# Radio.net
KiCad netlist of a schematic drawn in Altium Designer
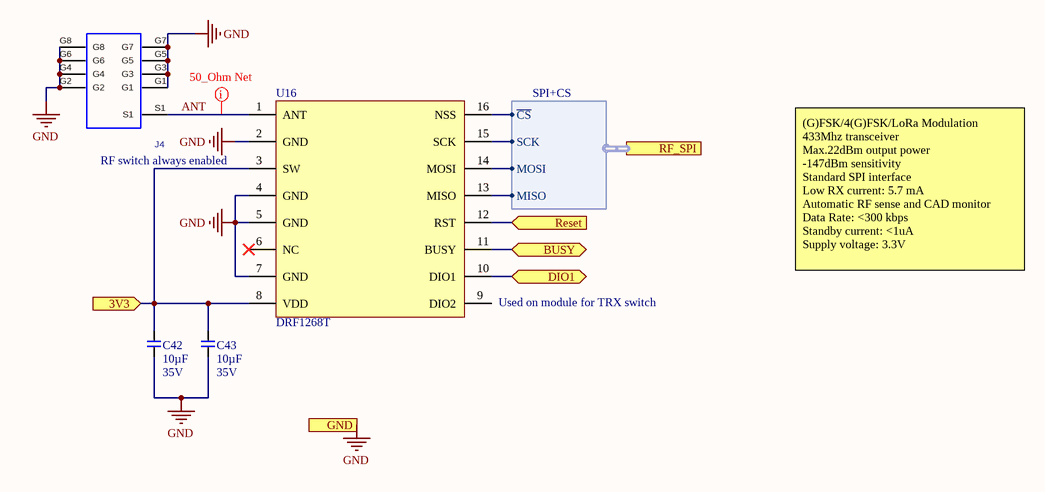
[diagram p0: Radio.SchDoc]

(export (version "E")
  (design (tool "Eeschema 10.0.6"))
  (components
    (comp (ref "C42")
      (value "490-13248-1-ND")
      (footprint "C0603")
      (description "CAP CER 10UF 35V X5R 0603 20%")
      (fields
        (field (name "CAPACITANCE (SHORTHAND)") "10µF")
        (field (name "RATED VOLTAGE") "35V")
        (field (name "MANUFACTURER") "Murata Electronics North America")
      )
      (libsource (lib "Stanford Student Space Initiative") (part "__template_cap"))
    )
    (comp (ref "C43")
      (value "490-13248-1-ND")
      (footprint "C0603")
      (description "CAP CER 10UF 35V X5R 0603 20%")
      (fields
        (field (name "CAPACITANCE (SHORTHAND)") "10µF")
        (field (name "RATED VOLTAGE") "35V")
        (field (name "MANUFACTURER") "Murata Electronics North America")
      )
      (libsource (lib "Stanford Student Space Initiative") (part "__template_cap"))
    )
    (comp (ref "J4")
      (value "SMA-J-P-X-ST-EM2")
      (footprint "SMA-J-P-X-ST-EM1")
      (libsource (lib "Stanford Student Space Initiative") (part "SMA-J-P-X-ST-EM1"))
    )
    (comp (ref "U16")
      (value "DRF1268T")
      (footprint "DRF1268T")
      (description "Dorji DRF1268T LoRa Module with SX1262 IC and TCXO")
      (libsource (lib "Stanford Student Space Initiative") (part "DRF1268T"))
    )
  )
  (nets
    (net (code "2") (name "/3V3") (class "Default")
      (node (ref "C42") (pin "1") (pintype "passive"))
      (node (ref "C43") (pin "1") (pintype "passive"))
      (node (ref "U16") (pin "3") (pinfunction "SW_3") (pintype "passive"))
      (node (ref "U16") (pin "8") (pinfunction "VDD_8") (pintype "passive"))
    )
    (net (code "3") (name "/ANT") (class "Default")
      (node (ref "J4") (pin "S1") (pinfunction "S1_S1") (pintype "passive"))
      (node (ref "U16") (pin "1") (pinfunction "ANT_1") (pintype "passive"))
    )
    (net (code "4") (name "/BUSY") (class "Default")
      (node (ref "U16") (pin "11") (pinfunction "BUSY_11") (pintype "passive"))
    )
    (net (code "5") (name "/DIO1") (class "Default")
      (node (ref "U16") (pin "10") (pinfunction "DIO1_10") (pintype "passive"))
    )
    (net (code "6") (name "/MISO") (class "Default")
      (node (ref "U16") (pin "13") (pinfunction "MISO_13") (pintype "passive"))
    )
    (net (code "7") (name "/MOSI") (class "Default")
      (node (ref "U16") (pin "14") (pinfunction "MOSI_14") (pintype "passive"))
    )
    (net (code "8") (name "/Reset") (class "Default")
      (node (ref "U16") (pin "12") (pinfunction "RST_12") (pintype "passive"))
    )
    (net (code "9") (name "/SCK") (class "Default")
      (node (ref "U16") (pin "15") (pinfunction "SCK_15") (pintype "passive"))
    )
    (net (code "11") (name "/~{CS}") (class "Default")
      (node (ref "U16") (pin "16") (pinfunction "NSS_16") (pintype "passive"))
    )
    (net (code "12") (name "GND") (class "Default")
      (node (ref "C42") (pin "2") (pintype "passive"))
      (node (ref "C43") (pin "2") (pintype "passive"))
      (node (ref "J4") (pin "G1") (pinfunction "G1_G1") (pintype "passive"))
      (node (ref "J4") (pin "G2") (pinfunction "G2_G2") (pintype "passive"))
      (node (ref "J4") (pin "G3") (pinfunction "G3_G3") (pintype "passive"))
      (node (ref "J4") (pin "G4") (pinfunction "G4_G4") (pintype "passive"))
      (node (ref "J4") (pin "G5") (pinfunction "G5_G5") (pintype "passive"))
      (node (ref "J4") (pin "G6") (pinfunction "G6_G6") (pintype "passive"))
      (node (ref "J4") (pin "G7") (pinfunction "G7_G7") (pintype "passive"))
      (node (ref "J4") (pin "G8") (pinfunction "G8_G8") (pintype "passive"))
      (node (ref "U16") (pin "2") (pinfunction "GND_2") (pintype "passive"))
      (node (ref "U16") (pin "4") (pinfunction "GND_4") (pintype "passive"))
      (node (ref "U16") (pin "5") (pinfunction "GND_5") (pintype "passive"))
      (node (ref "U16") (pin "7") (pinfunction "GND_7") (pintype "passive"))
    )
    (net (code "13") (name "unconnected-(U16-DIO2-Pad9)") (class "Default")
      (node (ref "U16") (pin "9") (pinfunction "DIO2_9") (pintype "passive"))
    )
    (net (code "14") (name "unconnected-(U16-NC-Pad6)") (class "Default")
      (node (ref "U16") (pin "6") (pinfunction "NC_6") (pintype "passive+no_connect"))
    )
  )
)
